# oled_mod.net
KiCad netlist of a schematic drawn in EAGLE
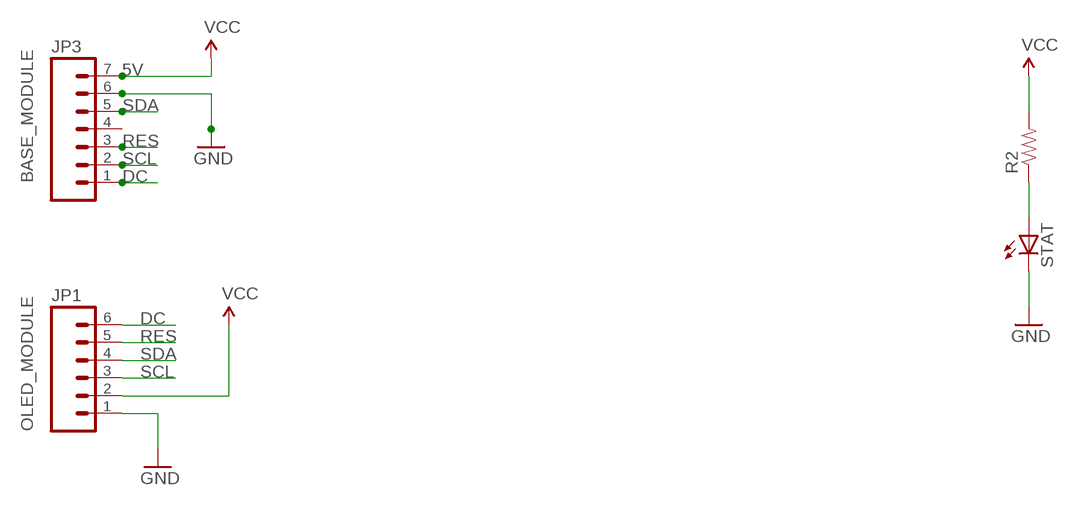
[diagram p0: schematic, sheet 1]

(export (version "E")
  (design (tool "Eeschema 10.0.6"))
  (components
    (comp (ref "JP1")
      (value "M06SILK_FEMALE_PTH")
      (footprint "eagle-import:1X06")
      (libsource (lib "eagle-import") (part "M06SILK_FEMALE_PTH"))
    )
    (comp (ref "JP3")
      (value "M07")
      (footprint "eagle-import:1X07")
      (libsource (lib "eagle-import") (part "M07"))
    )
    (comp (ref "R2")
      (value "RESISTOR0805-RES")
      (footprint "eagle-import:0805")
      (libsource (lib "eagle-import") (part "RESISTOR0805-RES"))
    )
    (comp (ref "STAT")
      (value "LEDCHIP-LED0805")
      (footprint "eagle-import:CHIP-LED0805")
      (libsource (lib "eagle-import") (part "LEDCHIP-LED0805"))
    )
  )
  (nets
    (net (code "1") (name "/DC") (class "Default")
      (node (ref "JP1") (pin "6") (pinfunction "6_6") (pintype "passive"))
      (node (ref "JP3") (pin "1") (pinfunction "1_1") (pintype "passive"))
    )
    (net (code "2") (name "/RES") (class "Default")
      (node (ref "JP1") (pin "5") (pinfunction "5_5") (pintype "passive"))
      (node (ref "JP3") (pin "3") (pinfunction "3_3") (pintype "passive"))
    )
    (net (code "3") (name "/SCL") (class "Default")
      (node (ref "JP1") (pin "3") (pinfunction "3_3") (pintype "passive"))
      (node (ref "JP3") (pin "2") (pinfunction "2_2") (pintype "passive"))
    )
    (net (code "4") (name "/SDA") (class "Default")
      (node (ref "JP1") (pin "4") (pinfunction "4_4") (pintype "passive"))
      (node (ref "JP3") (pin "5") (pinfunction "5_5") (pintype "passive"))
    )
    (net (code "5") (name "GND") (class "Default")
      (node (ref "JP1") (pin "1") (pinfunction "1_1") (pintype "passive"))
      (node (ref "JP3") (pin "6") (pinfunction "6_6") (pintype "passive"))
      (node (ref "STAT") (pin "C") (pinfunction "C_C") (pintype "passive"))
    )
    (net (code "6") (name "Net-(R2-Pad1)") (class "Default")
      (node (ref "R2") (pin "1") (pinfunction "1_1") (pintype "passive"))
      (node (ref "STAT") (pin "A") (pinfunction "A_A") (pintype "passive"))
    )
    (net (code "7") (name "VCC") (class "Default")
      (node (ref "JP1") (pin "2") (pinfunction "2_2") (pintype "passive"))
      (node (ref "JP3") (pin "7") (pinfunction "7_7") (pintype "passive"))
      (node (ref "R2") (pin "2") (pinfunction "2_2") (pintype "passive"))
    )
    (net (code "8") (name "unconnected-(JP3-Pad4)") (class "Default")
      (node (ref "JP3") (pin "4") (pinfunction "4_4") (pintype "passive"))
    )
  )
)
